# Solar_ESC_AM32.net
KiCad netlist of a schematic drawn in Altium Designer
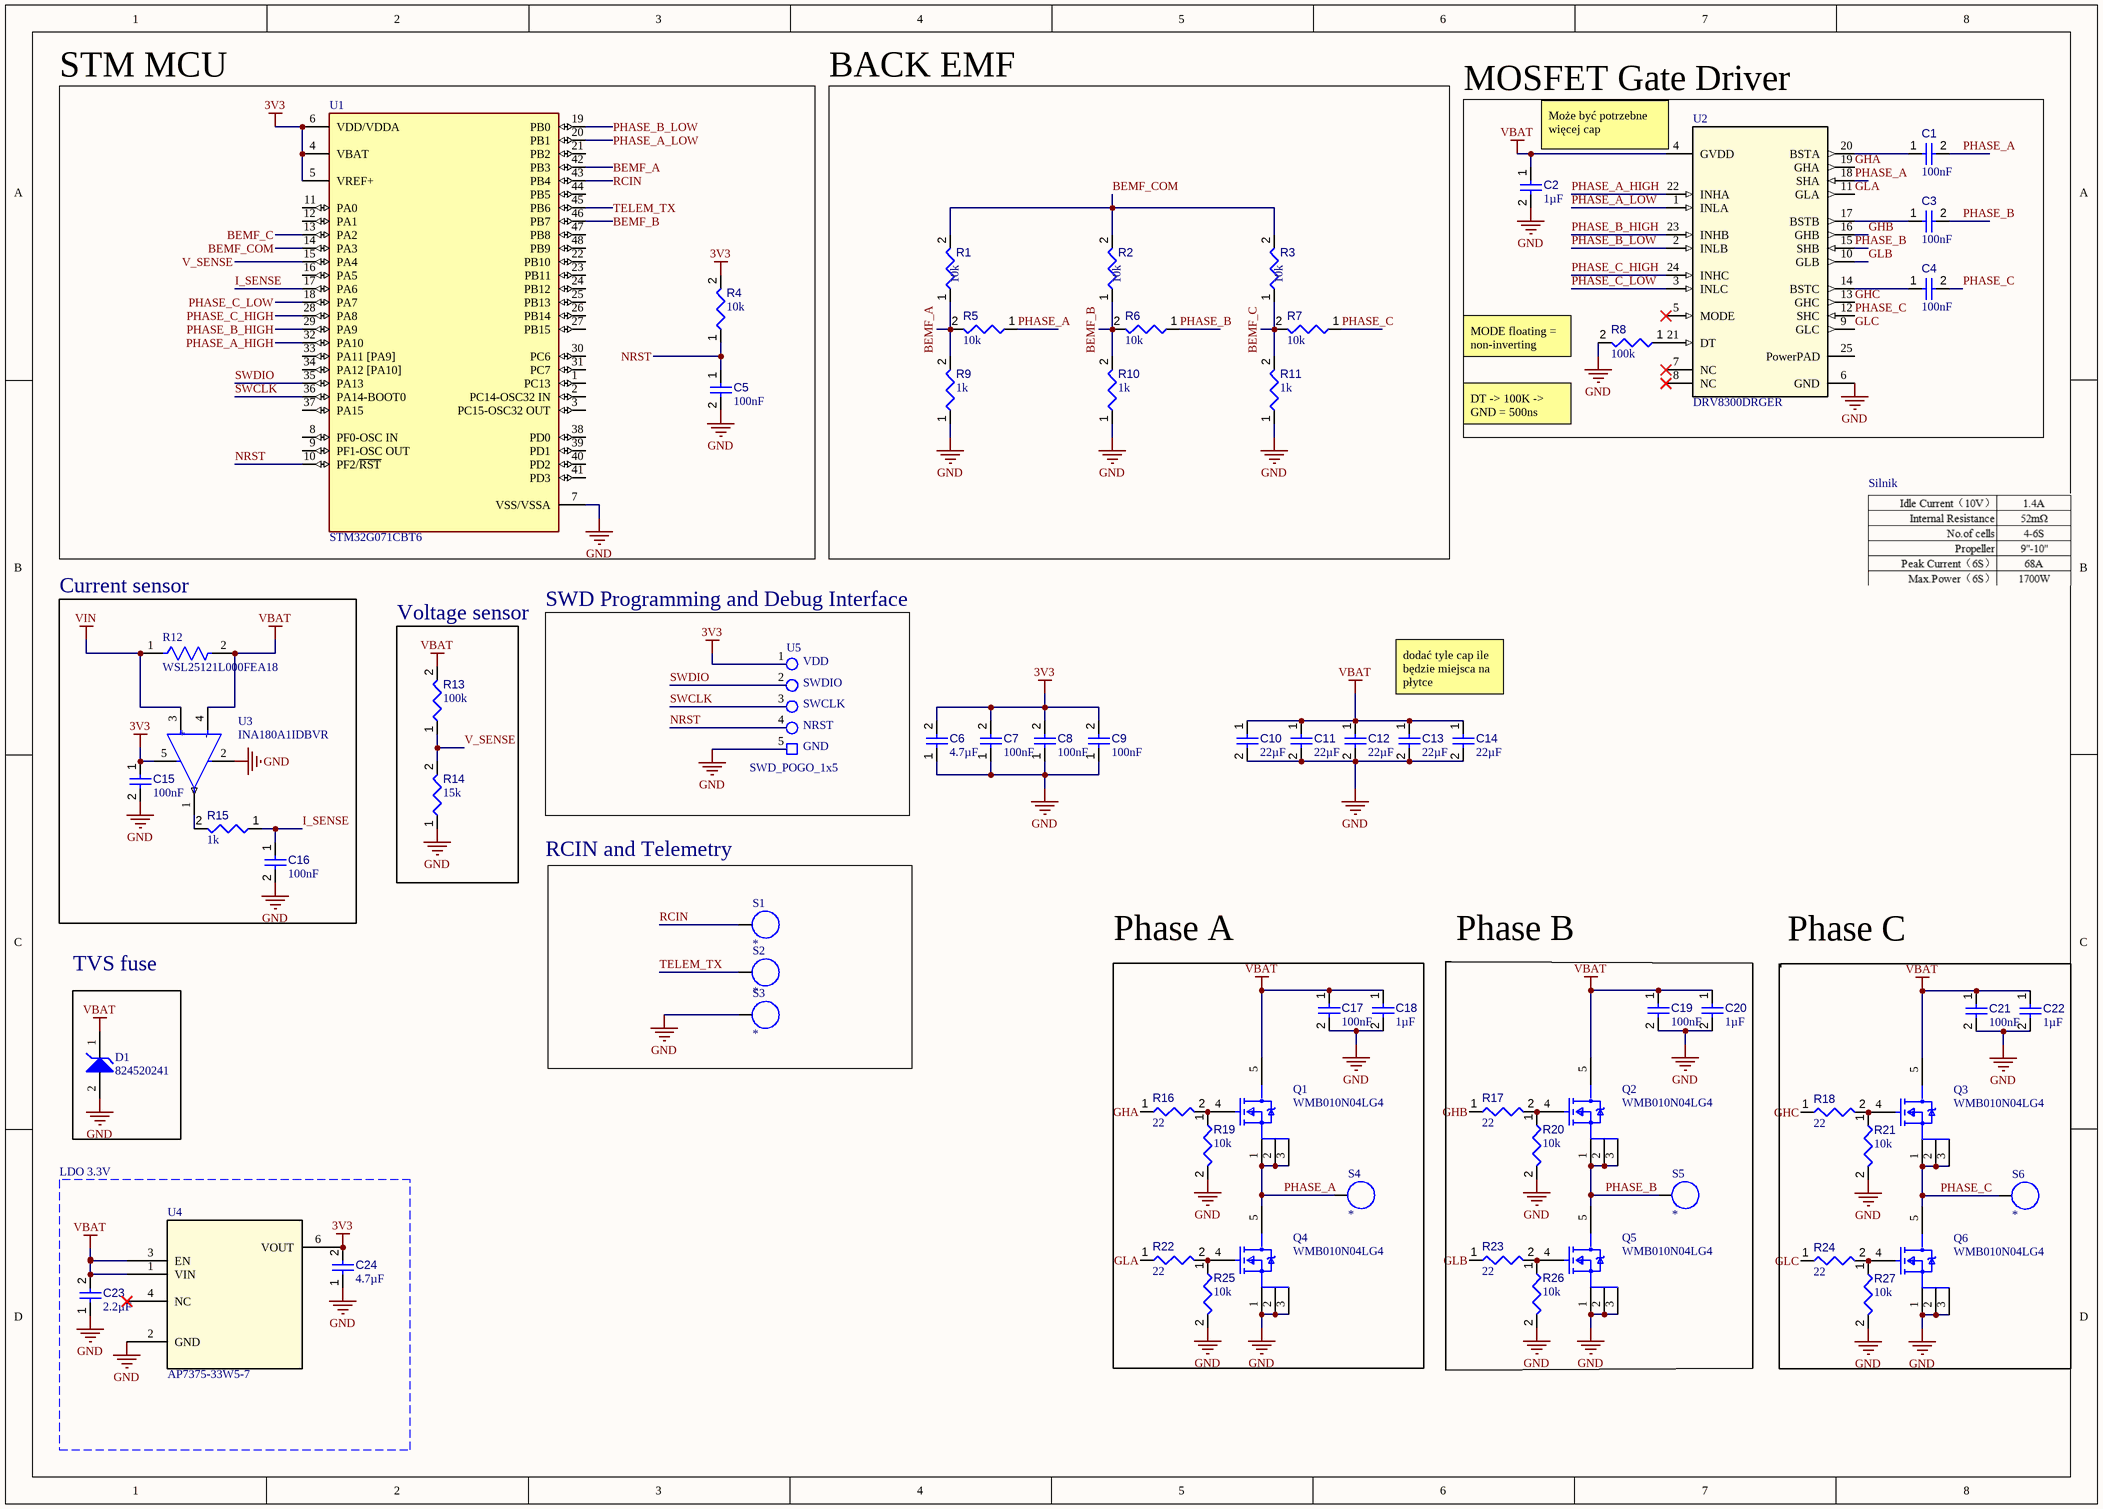
[diagram p0: Solar_ESC_AM32.SchDoc]

(export (version "E")
  (design (tool "Eeschema 10.0.6"))
  (components
    (comp (ref "C1")
      (value "100nF")
      (footprint "CAPC0805(2012)145_L")
      (description "Chip Capacitor, 0.1µF +/-40%, 25V, 0805, Thickness 1.45 mm")
      (fields (field (name "TOLERANCE") "20%") (field (name "Comment") "Capacitor 0.1µF +/-40% 25V 0805"))
      (libsource (lib "Solar_Plane_Jakub_Konior") (part "CAP-NP-2"))
    )
    (comp (ref "C2")
      (value "1µF")
      (footprint "CAPC0805(2012)145_L")
      (description "Chip Capacitor, 1µF +/-40%, 25V, 0805, Thickness 1.45 mm")
      (fields (field (name "TOLERANCE") "20%") (field (name "Comment") "Capacitor 1µF +/-40% 25V 0805"))
      (libsource (lib "Solar_Plane_Jakub_Konior") (part "CAP-NP-2"))
    )
    (comp (ref "C3")
      (value "100nF")
      (footprint "CAPC0805(2012)145_L")
      (description "Chip Capacitor, 0.1µF +/-40%, 25V, 0805, Thickness 1.45 mm")
      (fields (field (name "TOLERANCE") "20%") (field (name "Comment") "Capacitor 0.1µF +/-40% 25V 0805"))
      (libsource (lib "Solar_Plane_Jakub_Konior") (part "CAP-NP-2"))
    )
    (comp (ref "C4")
      (value "100nF")
      (footprint "CAPC0805(2012)145_L")
      (description "Chip Capacitor, 0.1µF +/-40%, 25V, 0805, Thickness 1.45 mm")
      (fields (field (name "TOLERANCE") "20%") (field (name "Comment") "Capacitor 0.1µF +/-40% 25V 0805"))
      (libsource (lib "Solar_Plane_Jakub_Konior") (part "CAP-NP-2"))
    )
    (comp (ref "C5")
      (value "100nF")
      (footprint "CAPC0805(2012)145_L")
      (description "Chip Capacitor, 100nF +/-40%, 6.3V, 0805, Thickness 1.45 mm")
      (fields (field (name "TOLERANCE") "10%") (field (name "Comment") "Capacitor 100nF +/-40% 6.3V 0805"))
      (libsource (lib "Solar_Plane_Jakub_Konior") (part "CAP-NP-2"))
    )
    (comp (ref "C6")
      (value "4.7µF")
      (footprint "CAPC0805(2012)145_L")
      (description "Chip Capacitor, 4.7µF +/-40%, 25V, 0805, Thickness 1.45 mm")
      (fields (field (name "TOLERANCE") "20%") (field (name "Comment") "Capacitor 4.7µF +/-40% 25V 0805"))
      (libsource (lib "Solar_Plane_Jakub_Konior") (part "CAP-NP-2"))
    )
    (comp (ref "C7")
      (value "100nF")
      (footprint "CAPC0805(2012)145_L")
      (description "Chip Capacitor, 0.1µF +/-40%, 25V, 0805, Thickness 1.45 mm")
      (fields (field (name "TOLERANCE") "20%") (field (name "Comment") "Capacitor 0.1µF +/-40% 25V 0805"))
      (libsource (lib "Solar_Plane_Jakub_Konior") (part "CAP-NP-2"))
    )
    (comp (ref "C8")
      (value "100nF")
      (footprint "CAPC0805(2012)145_L")
      (description "Chip Capacitor, 0.1µF +/-40%, 25V, 0805, Thickness 1.45 mm")
      (fields (field (name "TOLERANCE") "20%") (field (name "Comment") "Capacitor 0.1µF +/-40% 25V 0805"))
      (libsource (lib "Solar_Plane_Jakub_Konior") (part "CAP-NP-2"))
    )
    (comp (ref "C9")
      (value "100nF")
      (footprint "CAPC0805(2012)145_L")
      (description "Chip Capacitor, 0.1µF +/-40%, 25V, 0805, Thickness 1.45 mm")
      (fields (field (name "TOLERANCE") "20%") (field (name "Comment") "Capacitor 0.1µF +/-40% 25V 0805"))
      (libsource (lib "Solar_Plane_Jakub_Konior") (part "CAP-NP-2"))
    )
    (comp (ref "C10")
      (value "22µF")
      (footprint "CAPC0805(2012)145_L")
      (description "Chip Capacitor, 22µF +/-40%, 16V, 0805, Thickness 1.45 mm")
      (fields (field (name "TOLERANCE") "5%") (field (name "Comment") "Capacitor 22µF +/-40% 16V 0805"))
      (libsource (lib "Solar_Plane_Jakub_Konior") (part "CAP-NP-2"))
    )
    (comp (ref "C11")
      (value "22µF")
      (footprint "CAPC0805(2012)145_L")
      (description "Chip Capacitor, 22µF +/-40%, 16V, 0805, Thickness 1.45 mm")
      (fields (field (name "TOLERANCE") "5%") (field (name "Comment") "Capacitor 22µF +/-40% 16V 0805"))
      (libsource (lib "Solar_Plane_Jakub_Konior") (part "CAP-NP-2"))
    )
    (comp (ref "C12")
      (value "22µF")
      (footprint "CAPC0805(2012)145_L")
      (description "Chip Capacitor, 22µF +/-40%, 16V, 0805, Thickness 1.45 mm")
      (fields (field (name "TOLERANCE") "5%") (field (name "Comment") "Capacitor 22µF +/-40% 16V 0805"))
      (libsource (lib "Solar_Plane_Jakub_Konior") (part "CAP-NP-2"))
    )
    (comp (ref "C13")
      (value "22µF")
      (footprint "CAPC0805(2012)145_L")
      (description "Chip Capacitor, 22µF +/-40%, 16V, 0805, Thickness 1.45 mm")
      (fields (field (name "TOLERANCE") "5%") (field (name "Comment") "Capacitor 22µF +/-40% 16V 0805"))
      (libsource (lib "Solar_Plane_Jakub_Konior") (part "CAP-NP-2"))
    )
    (comp (ref "C14")
      (value "22µF")
      (footprint "CAPC0805(2012)145_L")
      (description "Chip Capacitor, 22µF +/-40%, 16V, 0805, Thickness 1.45 mm")
      (fields (field (name "TOLERANCE") "5%") (field (name "Comment") "Capacitor 22µF +/-40% 16V 0805"))
      (libsource (lib "Solar_Plane_Jakub_Konior") (part "CAP-NP-2"))
    )
    (comp (ref "C15")
      (value "100nF")
      (footprint "CAPC0805(2012)145_L")
      (description "Chip Capacitor, 0.1µF +/-40%, 25V, 0805, Thickness 1.45 mm")
      (fields (field (name "TOLERANCE") "20%") (field (name "Comment") "Capacitor 0.1µF +/-40% 25V 0805"))
      (libsource (lib "Solar_Plane_Jakub_Konior") (part "CAP-NP-2"))
    )
    (comp (ref "C16")
      (value "100nF")
      (footprint "CAPC0805(2012)145_L")
      (description "Chip Capacitor, 0.1µF +/-40%, 25V, 0805, Thickness 1.45 mm")
      (fields (field (name "TOLERANCE") "20%") (field (name "Comment") "Capacitor 0.1µF +/-40% 25V 0805"))
      (libsource (lib "Solar_Plane_Jakub_Konior") (part "CAP-NP-2"))
    )
    (comp (ref "C17")
      (value "100nF")
      (footprint "CAPC0805(2012)145_L")
      (description "Chip Capacitor, 100nF +/-40%, 6.3V, 0805, Thickness 1.45 mm")
      (fields (field (name "TOLERANCE") "10%") (field (name "Comment") "Capacitor 100nF +/-40% 6.3V 0805"))
      (libsource (lib "Solar_Plane_Jakub_Konior") (part "CAP-NP-2"))
    )
    (comp (ref "C18")
      (value "1µF")
      (footprint "CAPC0805(2012)145_L")
      (description "Chip Capacitor, 1µF +/-40%, 25V, 0805, Thickness 1.45 mm")
      (fields (field (name "TOLERANCE") "20%") (field (name "Comment") "Capacitor 1µF +/-40% 25V 0805"))
      (libsource (lib "Solar_Plane_Jakub_Konior") (part "CAP-NP-2"))
    )
    (comp (ref "C19")
      (value "100nF")
      (footprint "CAPC0805(2012)145_L")
      (description "Chip Capacitor, 100nF +/-40%, 6.3V, 0805, Thickness 1.45 mm")
      (fields (field (name "TOLERANCE") "10%") (field (name "Comment") "Capacitor 100nF +/-40% 6.3V 0805"))
      (libsource (lib "Solar_Plane_Jakub_Konior") (part "CAP-NP-2"))
    )
    (comp (ref "C20")
      (value "1µF")
      (footprint "CAPC0805(2012)145_L")
      (description "Chip Capacitor, 1µF +/-40%, 25V, 0805, Thickness 1.45 mm")
      (fields (field (name "TOLERANCE") "20%") (field (name "Comment") "Capacitor 1µF +/-40% 25V 0805"))
      (libsource (lib "Solar_Plane_Jakub_Konior") (part "CAP-NP-2"))
    )
    (comp (ref "C21")
      (value "100nF")
      (footprint "CAPC0805(2012)145_L")
      (description "Chip Capacitor, 100nF +/-40%, 6.3V, 0805, Thickness 1.45 mm")
      (fields (field (name "TOLERANCE") "10%") (field (name "Comment") "Capacitor 100nF +/-40% 6.3V 0805"))
      (libsource (lib "Solar_Plane_Jakub_Konior") (part "CAP-NP-2"))
    )
    (comp (ref "C22")
      (value "1µF")
      (footprint "CAPC0805(2012)145_L")
      (description "Chip Capacitor, 1µF +/-40%, 25V, 0805, Thickness 1.45 mm")
      (fields (field (name "TOLERANCE") "20%") (field (name "Comment") "Capacitor 1µF +/-40% 25V 0805"))
      (libsource (lib "Solar_Plane_Jakub_Konior") (part "CAP-NP-2"))
    )
    (comp (ref "C23")
      (value "2.2µF")
      (footprint "CAPC0805(2012)145_L")
      (description "Chip Capacitor, 2.2µF +/-40%, 35V, 0805, Thickness 1.45 mm")
      (fields (field (name "TOLERANCE") "20%") (field (name "Comment") "Capacitor 2.2µF +/-40% 35V 0805"))
      (libsource (lib "Solar_Plane_Jakub_Konior") (part "CAP-NP-2"))
    )
    (comp (ref "C24")
      (value "4.7µF")
      (footprint "CAPC0805(2012)145_L")
      (description "Chip Capacitor, 4.7µF +/-40%, 25V, 0805, Thickness 1.45 mm")
      (fields (field (name "TOLERANCE") "20%") (field (name "Comment") "Capacitor 4.7µF +/-40% 25V 0805"))
      (libsource (lib "Solar_Plane_Jakub_Konior") (part "CAP-NP-2"))
    )
    (comp (ref "D1")
      (value "824520241")
      (footprint "WE-TVSP_DO-214AA_Unidirectional")
      (description "TVS diode [Würth Elektronik] 824520241 TVS diode")
      (libsource (lib "Altium Content Vault") (part "WE-TVSP_Unidirectional"))
    )
    (comp (ref "Q1")
      (value "WMB010N04LG4")
      (footprint "TRANS_CMS42N10H8-HF")
      (description "N-MOSFET; unipolar; 40V; 268A; Idm: 1072A; 114W")
      (libsource (lib "Solar_ESC_AM32") (part "WMB010N04LG4"))
    )
    (comp (ref "Q2")
      (value "WMB010N04LG4")
      (footprint "TRANS_CMS42N10H8-HF")
      (description "N-MOSFET; unipolar; 40V; 268A; Idm: 1072A; 114W")
      (libsource (lib "Solar_ESC_AM32") (part "WMB010N04LG4"))
    )
    (comp (ref "Q3")
      (value "WMB010N04LG4")
      (footprint "TRANS_CMS42N10H8-HF")
      (description "N-MOSFET; unipolar; 40V; 268A; Idm: 1072A; 114W")
      (libsource (lib "Solar_ESC_AM32") (part "WMB010N04LG4"))
    )
    (comp (ref "Q4")
      (value "WMB010N04LG4")
      (footprint "TRANS_CMS42N10H8-HF")
      (description "N-MOSFET; unipolar; 40V; 268A; Idm: 1072A; 114W")
      (libsource (lib "Solar_ESC_AM32") (part "WMB010N04LG4"))
    )
    (comp (ref "Q5")
      (value "WMB010N04LG4")
      (footprint "TRANS_CMS42N10H8-HF")
      (description "N-MOSFET; unipolar; 40V; 268A; Idm: 1072A; 114W")
      (libsource (lib "Solar_ESC_AM32") (part "WMB010N04LG4"))
    )
    (comp (ref "Q6")
      (value "WMB010N04LG4")
      (footprint "TRANS_CMS42N10H8-HF")
      (description "N-MOSFET; unipolar; 40V; 268A; Idm: 1072A; 114W")
      (libsource (lib "Solar_ESC_AM32") (part "WMB010N04LG4"))
    )
    (comp (ref "R1")
      (value "10k")
      (footprint "RESC0402(1005)_L")
      (description "Chip Resistor, 10 kOhms, +/-1 %, 63 mW, -55 to 125 degC, 0402")
      (fields (field (name "POWER") "63mW") (field (name "TOLERANCE") "1%"))
      (libsource (lib "Solar_Plane_Jakub_Konior") (part "RES-2"))
    )
    (comp (ref "R2")
      (value "10k")
      (footprint "RESC0402(1005)_L")
      (description "Chip Resistor, 10 kOhms, +/-1 %, 63 mW, -55 to 125 degC, 0402")
      (fields (field (name "POWER") "63mW") (field (name "TOLERANCE") "1%"))
      (libsource (lib "Solar_Plane_Jakub_Konior") (part "RES-2"))
    )
    (comp (ref "R3")
      (value "10k")
      (footprint "RESC0402(1005)_L")
      (description "Chip Resistor, 10 kOhms, +/-1 %, 63 mW, -55 to 125 degC, 0402")
      (fields (field (name "POWER") "63mW") (field (name "TOLERANCE") "1%"))
      (libsource (lib "Solar_Plane_Jakub_Konior") (part "RES-2"))
    )
    (comp (ref "R4")
      (value "10k")
      (footprint "RESC0402(1005)_L")
      (description "Chip Resistor, 10 kOhms, +/-1 %, 63 mW, -55 to 125 degC, 0402")
      (fields (field (name "POWER") "63mW") (field (name "TOLERANCE") "1%"))
      (libsource (lib "Solar_Plane_Jakub_Konior") (part "RES-2"))
    )
    (comp (ref "R5")
      (value "10k")
      (footprint "RESC0402(1005)_L")
      (description "Chip Resistor, 10 kOhms, +/-1 %, 63 mW, -55 to 125 degC, 0402")
      (fields (field (name "POWER") "63mW") (field (name "TOLERANCE") "1%"))
      (libsource (lib "Solar_Plane_Jakub_Konior") (part "RES-2"))
    )
    (comp (ref "R6")
      (value "10k")
      (footprint "RESC0402(1005)_L")
      (description "Chip Resistor, 10 kOhms, +/-1 %, 63 mW, -55 to 125 degC, 0402")
      (fields (field (name "POWER") "63mW") (field (name "TOLERANCE") "1%"))
      (libsource (lib "Solar_Plane_Jakub_Konior") (part "RES-2"))
    )
    (comp (ref "R7")
      (value "10k")
      (footprint "RESC0402(1005)_L")
      (description "Chip Resistor, 10 kOhms, +/-1 %, 63 mW, -55 to 125 degC, 0402")
      (fields (field (name "POWER") "63mW") (field (name "TOLERANCE") "1%"))
      (libsource (lib "Solar_Plane_Jakub_Konior") (part "RES-2"))
    )
    (comp (ref "R8")
      (value "100k")
      (footprint "RESC0402(1005)_L")
      (description "Chip Resistor, 100 kOhms, +/-1 %, 63 mW, -55 to 155 degC, 0402")
      (fields (field (name "TOLERANCE") "1%") (field (name "POWER") "63mW"))
      (libsource (lib "Solar_Plane_Jakub_Konior") (part "RES-2"))
    )
    (comp (ref "R9")
      (value "1k")
      (footprint "RESC0402(1005)_L")
      (description "Chip Resistor, 1 kOhms, +/-5 %, 63 mW, -55 to 155 degC, 0402")
      (fields (field (name "TOLERANCE") "5%") (field (name "POWER") "63mW"))
      (libsource (lib "Solar_Plane_Jakub_Konior") (part "RES-2"))
    )
    (comp (ref "R10")
      (value "1k")
      (footprint "RESC0402(1005)_L")
      (description "Chip Resistor, 1 kOhms, +/-5 %, 63 mW, -55 to 155 degC, 0402")
      (fields (field (name "TOLERANCE") "5%") (field (name "POWER") "63mW"))
      (libsource (lib "Solar_Plane_Jakub_Konior") (part "RES-2"))
    )
    (comp (ref "R11")
      (value "1k")
      (footprint "RESC0402(1005)_L")
      (description "Chip Resistor, 1 kOhms, +/-5 %, 63 mW, -55 to 155 degC, 0402")
      (fields (field (name "TOLERANCE") "5%") (field (name "POWER") "63mW"))
      (libsource (lib "Solar_Plane_Jakub_Konior") (part "RES-2"))
    )
    (comp (ref "R12")
      (value "WSL25121L000FEA18")
      (footprint "FP-WSL2512-MFG")
      (fields (field (name "TOLERANCE") "1%"))
      (libsource (lib "Altium Content Vault") (part "1029c3af85768c4190bb7ad29bc67b5"))
    )
    (comp (ref "R13")
      (value "100k")
      (footprint "RESC0402(1005)_L")
      (description "Chip Resistor, 100 kOhms, +/-1 %, 63 mW, -55 to 155 degC, 0402")
      (fields (field (name "TOLERANCE") "1%") (field (name "POWER") "63mW"))
      (libsource (lib "Solar_Plane_Jakub_Konior") (part "RES-2"))
    )
    (comp (ref "R14")
      (value "15k")
      (footprint "RESC0402(1005)_L")
      (description "Chip Resistor, 15 kOhms, +/-1 %, 63 mW, -55 to 155 degC, 0402")
      (fields (field (name "TOLERANCE") "1%") (field (name "POWER") "63mW"))
      (libsource (lib "Solar_Plane_Jakub_Konior") (part "RES-2"))
    )
    (comp (ref "R15")
      (value "1k")
      (footprint "RESC0402(1005)_L")
      (description "Chip Resistor, 1 kOhms, +/-5 %, 63 mW, -55 to 155 degC, 0402")
      (fields (field (name "TOLERANCE") "5%") (field (name "POWER") "63mW"))
      (libsource (lib "Solar_Plane_Jakub_Konior") (part "RES-2"))
    )
    (comp (ref "R16")
      (value "22")
      (footprint "RESC1609X50X30ML08T20")
      (description "Chip Resistor, 22 Ohm, +/- 1%, 100 mW, -55 to 155 degC, 0603 (1608 Metric)")
      (fields (field (name "POWER") "100mW") (field (name "TOLERANCE") "1%"))
      (libsource (lib "Solar_Plane_Jakub_Konior") (part "RES-2"))
    )
    (comp (ref "R17")
      (value "22")
      (footprint "RESC1609X50X30ML08T20")
      (description "Chip Resistor, 22 Ohm, +/- 1%, 100 mW, -55 to 155 degC, 0603 (1608 Metric)")
      (fields (field (name "POWER") "100mW") (field (name "TOLERANCE") "1%"))
      (libsource (lib "Solar_Plane_Jakub_Konior") (part "RES-2"))
    )
    (comp (ref "R18")
      (value "22")
      (footprint "RESC1609X50X30ML08T20")
      (description "Chip Resistor, 22 Ohm, +/- 1%, 100 mW, -55 to 155 degC, 0603 (1608 Metric)")
      (fields (field (name "POWER") "100mW") (field (name "TOLERANCE") "1%"))
      (libsource (lib "Solar_Plane_Jakub_Konior") (part "RES-2"))
    )
    (comp (ref "R19")
      (value "10k")
      (footprint "RESC0402(1005)_L")
      (description "Chip Resistor, 10 kOhms, +/-1 %, 63 mW, -55 to 125 degC, 0402")
      (fields (field (name "POWER") "63mW") (field (name "TOLERANCE") "1%"))
      (libsource (lib "Solar_Plane_Jakub_Konior") (part "RES-2"))
    )
    (comp (ref "R20")
      (value "10k")
      (footprint "RESC0402(1005)_L")
      (description "Chip Resistor, 10 kOhms, +/-1 %, 63 mW, -55 to 125 degC, 0402")
      (fields (field (name "POWER") "63mW") (field (name "TOLERANCE") "1%"))
      (libsource (lib "Solar_Plane_Jakub_Konior") (part "RES-2"))
    )
    (comp (ref "R21")
      (value "10k")
      (footprint "RESC0402(1005)_L")
      (description "Chip Resistor, 10 kOhms, +/-1 %, 63 mW, -55 to 125 degC, 0402")
      (fields (field (name "POWER") "63mW") (field (name "TOLERANCE") "1%"))
      (libsource (lib "Solar_Plane_Jakub_Konior") (part "RES-2"))
    )
    (comp (ref "R22")
      (value "22")
      (footprint "RESC1609X50X30ML08T20")
      (description "Chip Resistor, 22 Ohm, +/- 1%, 100 mW, -55 to 155 degC, 0603 (1608 Metric)")
      (fields (field (name "POWER") "100mW") (field (name "TOLERANCE") "1%"))
      (libsource (lib "Solar_Plane_Jakub_Konior") (part "RES-2"))
    )
    (comp (ref "R23")
      (value "22")
      (footprint "RESC1609X50X30ML08T20")
      (description "Chip Resistor, 22 Ohm, +/- 1%, 100 mW, -55 to 155 degC, 0603 (1608 Metric)")
      (fields (field (name "POWER") "100mW") (field (name "TOLERANCE") "1%"))
      (libsource (lib "Solar_Plane_Jakub_Konior") (part "RES-2"))
    )
    (comp (ref "R24")
      (value "22")
      (footprint "RESC1609X50X30ML08T20")
      (description "Chip Resistor, 22 Ohm, +/- 1%, 100 mW, -55 to 155 degC, 0603 (1608 Metric)")
      (fields (field (name "POWER") "100mW") (field (name "TOLERANCE") "1%"))
      (libsource (lib "Solar_Plane_Jakub_Konior") (part "RES-2"))
    )
    (comp (ref "R25")
      (value "10k")
      (footprint "RESC0402(1005)_L")
      (description "Chip Resistor, 10 kOhms, +/-1 %, 63 mW, -55 to 125 degC, 0402")
      (fields (field (name "POWER") "63mW") (field (name "TOLERANCE") "1%"))
      (libsource (lib "Solar_Plane_Jakub_Konior") (part "RES-2"))
    )
    (comp (ref "R26")
      (value "10k")
      (footprint "RESC0402(1005)_L")
      (description "Chip Resistor, 10 kOhms, +/-1 %, 63 mW, -55 to 125 degC, 0402")
      (fields (field (name "POWER") "63mW") (field (name "TOLERANCE") "1%"))
      (libsource (lib "Solar_Plane_Jakub_Konior") (part "RES-2"))
    )
    (comp (ref "R27")
      (value "10k")
      (footprint "RESC0402(1005)_L")
      (description "Chip Resistor, 10 kOhms, +/-1 %, 63 mW, -55 to 125 degC, 0402")
      (fields (field (name "POWER") "63mW") (field (name "TOLERANCE") "1%"))
      (libsource (lib "Solar_Plane_Jakub_Konior") (part "RES-2"))
    )
    (comp (ref "S1")
      (value "*")
      (footprint "SOLDER_PAD_SIGNAL")
      (libsource (lib "Solar_ESC_AM32") (part "SolderPad"))
    )
    (comp (ref "S2")
      (value "*")
      (footprint "SOLDER_PAD_SIGNAL")
      (libsource (lib "Solar_ESC_AM32") (part "SolderPad"))
    )
    (comp (ref "S3")
      (value "*")
      (footprint "SOLDER_PAD_SIGNAL")
      (libsource (lib "Solar_ESC_AM32") (part "SolderPad"))
    )
    (comp (ref "S4")
      (value "*")
      (footprint "SOLDER_PAD_PHASE")
      (libsource (lib "Solar_ESC_AM32") (part "SolderPad"))
    )
    (comp (ref "S5")
      (value "*")
      (footprint "SOLDER_PAD_PHASE")
      (libsource (lib "Solar_ESC_AM32") (part "SolderPad"))
    )
    (comp (ref "S6")
      (value "*")
      (footprint "SOLDER_PAD_PHASE")
      (libsource (lib "Solar_ESC_AM32") (part "SolderPad"))
    )
    (comp (ref "U1")
      (value "STM32G071CBT6")
      (footprint "FP-LQFP48-5B-MFG")
      (description "IC MCU 32BIT 128KB FLASH 48LQFP")
      (fields
        (field (name "OCTOPART") "https://octopart.com/stm32g071cbt6-stmicroelectronics-96627027")
        (field (name "MANUFACTURER") "STMicroelectronics")
      )
      (libsource (lib "Altium Content Vault") (part "c9f63a35dbd129b66bfedb266152198"))
    )
    (comp (ref "U2")
      (value "DRV8300DRGER")
      (footprint "RGE0024B-IPC_B")
      (description "100-V max simple 3-phase gate driver with bootstrap diodes 24-VQFN -40 to 125")
      (fields (field (name "COPYRIGHT") "Copyright (C) 2025 Ultra Librarian. All rights reserved."))
      (libsource (lib "Solar_ESC_AM32") (part "DRV8300DRGER"))
    )
    (comp (ref "U3")
      (value "INA180A1IDBVR")
      (footprint "FP-DBV0005A-IPC_A")
      (description "IC CURR SENSE 1 CIRCUIT SOT23-5")
      (libsource (lib "Altium Content Vault") (part "0a55cf1a948ad01a3239aec1b7efad0"))
    )
    (comp (ref "U4")
      (value "AP7375-33W5-7")
      (footprint "SOT25_AP7375-33W5-7_DIO")
      (description "Description")
      (fields (field (name "COPYRIGHT") "Copyright (C) 2026 Ultra Librarian. All rights reserved."))
      (libsource (lib "AP7375-33W5-7") (part "AP7375-33W5-7"))
    )
    (comp (ref "U5")
      (value "SWD_POGO_1x5")
      (footprint "SWD_pogo_testpoints")
      (libsource (lib "Solar_ESC_AM32") (part "SWD_POGO_1x5"))
    )
  )
  (nets
    (net (code "2") (name "/BEMF_A") (class "Default")
      (node (ref "R1") (pin "1") (pinfunction "1_1") (pintype "passive"))
      (node (ref "R5") (pin "2") (pinfunction "2_2") (pintype "passive"))
      (node (ref "R9") (pin "2") (pinfunction "2_2") (pintype "passive"))
      (node (ref "U1") (pin "42") (pinfunction "PB3_42") (pintype "bidirectional"))
    )
    (net (code "3") (name "/BEMF_B") (class "Default")
      (node (ref "R10") (pin "2") (pinfunction "2_2") (pintype "passive"))
      (node (ref "R2") (pin "1") (pinfunction "1_1") (pintype "passive"))
      (node (ref "R6") (pin "2") (pinfunction "2_2") (pintype "passive"))
      (node (ref "U1") (pin "46") (pinfunction "PB7_46") (pintype "bidirectional"))
    )
    (net (code "4") (name "/BEMF_C") (class "Default")
      (node (ref "R11") (pin "2") (pinfunction "2_2") (pintype "passive"))
      (node (ref "R3") (pin "1") (pinfunction "1_1") (pintype "passive"))
      (node (ref "R7") (pin "2") (pinfunction "2_2") (pintype "passive"))
      (node (ref "U1") (pin "13") (pinfunction "PA2_13") (pintype "bidirectional"))
    )
    (net (code "5") (name "/BEMF_COM") (class "Default")
      (node (ref "R1") (pin "2") (pinfunction "2_2") (pintype "passive"))
      (node (ref "R2") (pin "2") (pinfunction "2_2") (pintype "passive"))
      (node (ref "R3") (pin "2") (pinfunction "2_2") (pintype "passive"))
      (node (ref "U1") (pin "14") (pinfunction "PA3_14") (pintype "bidirectional"))
    )
    (net (code "6") (name "/GHA") (class "Default")
      (node (ref "R16") (pin "1") (pinfunction "1_1") (pintype "passive"))
      (node (ref "U2") (pin "19") (pinfunction "GHA_19") (pintype "output"))
    )
    (net (code "7") (name "/GHB") (class "Default")
      (node (ref "R17") (pin "1") (pinfunction "1_1") (pintype "passive"))
      (node (ref "U2") (pin "16") (pinfunction "GHB_16") (pintype "output"))
    )
    (net (code "8") (name "/GHC") (class "Default")
      (node (ref "R18") (pin "1") (pinfunction "1_1") (pintype "passive"))
      (node (ref "U2") (pin "13") (pinfunction "GHC_13") (pintype "output"))
    )
    (net (code "9") (name "/GLA") (class "Default")
      (node (ref "R22") (pin "1") (pinfunction "1_1") (pintype "passive"))
      (node (ref "U2") (pin "11") (pinfunction "GLA_11") (pintype "output"))
    )
    (net (code "10") (name "/GLB") (class "Default")
      (node (ref "R23") (pin "1") (pinfunction "1_1") (pintype "passive"))
      (node (ref "U2") (pin "10") (pinfunction "GLB_10") (pintype "output"))
    )
    (net (code "11") (name "/GLC") (class "Default")
      (node (ref "R24") (pin "1") (pinfunction "1_1") (pintype "passive"))
      (node (ref "U2") (pin "9") (pinfunction "GLC_9") (pintype "output"))
    )
    (net (code "12") (name "/I_SENSE") (class "Default")
      (node (ref "C16") (pin "1") (pinfunction "1_1") (pintype "passive"))
      (node (ref "R15") (pin "1") (pinfunction "1_1") (pintype "passive"))
      (node (ref "U1") (pin "17") (pinfunction "PA6_17") (pintype "bidirectional"))
    )
    (net (code "13") (name "/NRST") (class "Default")
      (node (ref "C5") (pin "1") (pinfunction "1_1") (pintype "passive"))
      (node (ref "R4") (pin "1") (pinfunction "1_1") (pintype "passive"))
      (node (ref "U1") (pin "10") (pinfunction "PF2/~{RST}_10") (pintype "bidirectional"))
      (node (ref "U5") (pin "4") (pinfunction "NRST_4") (pintype "passive"))
    )
    (net (code "14") (name "/PHASE_A") (class "Default")
      (node (ref "C1") (pin "2") (pinfunction "2_2") (pintype "passive"))
      (node (ref "Q1") (pin "1") (pinfunction "S_1") (pintype "passive"))
      (node (ref "Q1") (pin "2") (pinfunction "S_2") (pintype "passive"))
      (node (ref "Q1") (pin "3") (pinfunction "S_3") (pintype "passive"))
      (node (ref "Q4") (pin "5") (pinfunction "D_5") (pintype "passive"))
      (node (ref "R5") (pin "1") (pinfunction "1_1") (pintype "passive"))
      (node (ref "S4") (pin "1") (pintype "passive"))
      (node (ref "U2") (pin "18") (pinfunction "SHA_18") (pintype "input"))
    )
    (net (code "15") (name "/PHASE_A_HIGH") (class "Default")
      (node (ref "U1") (pin "32") (pinfunction "PA10_32") (pintype "bidirectional"))
      (node (ref "U2") (pin "22") (pinfunction "INHA_22") (pintype "input"))
    )
    (net (code "16") (name "/PHASE_A_LOW") (class "Default")
      (node (ref "U1") (pin "20") (pinfunction "PB1_20") (pintype "bidirectional"))
      (node (ref "U2") (pin "1") (pinfunction "INLA_1") (pintype "input"))
    )
    (net (code "17") (name "/PHASE_B") (class "Default")
      (node (ref "C3") (pin "2") (pinfunction "2_2") (pintype "passive"))
      (node (ref "Q2") (pin "1") (pinfunction "S_1") (pintype "passive"))
      (node (ref "Q2") (pin "2") (pinfunction "S_2") (pintype "passive"))
      (node (ref "Q2") (pin "3") (pinfunction "S_3") (pintype "passive"))
      (node (ref "Q5") (pin "5") (pinfunction "D_5") (pintype "passive"))
      (node (ref "R6") (pin "1") (pinfunction "1_1") (pintype "passive"))
      (node (ref "S5") (pin "1") (pintype "passive"))
      (node (ref "U2") (pin "15") (pinfunction "SHB_15") (pintype "input"))
    )
    (net (code "18") (name "/PHASE_B_HIGH") (class "Default")
      (node (ref "U1") (pin "29") (pinfunction "PA9_29") (pintype "bidirectional"))
      (node (ref "U2") (pin "23") (pinfunction "INHB_23") (pintype "input"))
    )
    (net (code "19") (name "/PHASE_B_LOW") (class "Default")
      (node (ref "U1") (pin "19") (pinfunction "PB0_19") (pintype "bidirectional"))
      (node (ref "U2") (pin "2") (pinfunction "INLB_2") (pintype "input"))
    )
    (net (code "20") (name "/PHASE_C") (class "Default")
      (node (ref "C4") (pin "2") (pinfunction "2_2") (pintype "passive"))
      (node (ref "Q3") (pin "1") (pinfunction "S_1") (pintype "passive"))
      (node (ref "Q3") (pin "2") (pinfunction "S_2") (pintype "passive"))
      (node (ref "Q3") (pin "3") (pinfunction "S_3") (pintype "passive"))
      (node (ref "Q6") (pin "5") (pinfunction "D_5") (pintype "passive"))
      (node (ref "R7") (pin "1") (pinfunction "1_1") (pintype "passive"))
      (node (ref "S6") (pin "1") (pintype "passive"))
      (node (ref "U2") (pin "12") (pinfunction "SHC_12") (pintype "input"))
    )
    (net (code "21") (name "/PHASE_C_HIGH") (class "Default")
      (node (ref "U1") (pin "28") (pinfunction "PA8_28") (pintype "bidirectional"))
      (node (ref "U2") (pin "24") (pinfunction "INHC_24") (pintype "input"))
    )
    (net (code "22") (name "/PHASE_C_LOW") (class "Default")
      (node (ref "U1") (pin "18") (pinfunction "PA7_18") (pintype "bidirectional"))
      (node (ref "U2") (pin "3") (pinfunction "INLC_3") (pintype "input"))
    )
    (net (code "23") (name "/RCIN") (class "Default")
      (node (ref "S1") (pin "1") (pintype "passive"))
      (node (ref "U1") (pin "43") (pinfunction "PB4_43") (pintype "bidirectional"))
    )
    (net (code "24") (name "/SWCLK") (class "Default")
      (node (ref "U1") (pin "36") (pinfunction "PA14-BOOT0_36") (pintype "bidirectional"))
      (node (ref "U5") (pin "3") (pinfunction "SWCLK_3") (pintype "passive"))
    )
    (net (code "25") (name "/SWDIO") (class "Default")
      (node (ref "U1") (pin "35") (pinfunction "PA13_35") (pintype "bidirectional"))
      (node (ref "U5") (pin "2") (pinfunction "SWDIO_2") (pintype "passive"))
    )
    (net (code "26") (name "/TELEM_TX") (class "Default")
      (node (ref "S2") (pin "1") (pintype "passive"))
      (node (ref "U1") (pin "45") (pinfunction "PB6_45") (pintype "bidirectional"))
    )
    (net (code "27") (name "/V_SENSE") (class "Default")
      (node (ref "R13") (pin "1") (pinfunction "1_1") (pintype "passive"))
      (node (ref "R14") (pin "2") (pinfunction "2_2") (pintype "passive"))
      (node (ref "U1") (pin "15") (pinfunction "PA4_15") (pintype "bidirectional"))
    )
    (net (code "28") (name "3V3") (class "Default")
      (node (ref "C15") (pin "1") (pinfunction "1_1") (pintype "passive"))
      (node (ref "C24") (pin "2") (pinfunction "2_2") (pintype "passive"))
      (node (ref "C6") (pin "2") (pinfunction "2_2") (pintype "passive"))
      (node (ref "C7") (pin "2") (pinfunction "2_2") (pintype "passive"))
      (node (ref "C8") (pin "2") (pinfunction "2_2") (pintype "passive"))
      (node (ref "C9") (pin "2") (pinfunction "2_2") (pintype "passive"))
      (node (ref "R4") (pin "2") (pinfunction "2_2") (pintype "passive"))
      (node (ref "U1") (pin "4") (pinfunction "VBAT_4") (pintype "power_in"))
      (node (ref "U1") (pin "5") (pinfunction "VREF+_5") (pintype "power_in"))
      (node (ref "U1") (pin "6") (pinfunction "VDD/VDDA_6") (pintype "power_in"))
      (node (ref "U3") (pin "5") (pinfunction "VS_5") (pintype "power_in"))
      (node (ref "U4") (pin "6") (pinfunction "VOUT_6") (pintype "power_in"))
      (node (ref "U5") (pin "1") (pinfunction "VCC_1") (pintype "passive"))
    )
    (net (code "29") (name "GND") (class "Default")
      (node (ref "C10") (pin "2") (pinfunction "2_2") (pintype "passive"))
      (node (ref "C11") (pin "2") (pinfunction "2_2") (pintype "passive"))
      (node (ref "C12") (pin "2") (pinfunction "2_2") (pintype "passive"))
      (node (ref "C13") (pin "2") (pinfunction "2_2") (pintype "passive"))
      (node (ref "C14") (pin "2") (pinfunction "2_2") (pintype "passive"))
      (node (ref "C15") (pin "2") (pinfunction "2_2") (pintype "passive"))
      (node (ref "C16") (pin "2") (pinfunction "2_2") (pintype "passive"))
      (node (ref "C17") (pin "2") (pinfunction "2_2") (pintype "passive"))
      (node (ref "C18") (pin "2") (pinfunction "2_2") (pintype "passive"))
      (node (ref "C19") (pin "2") (pinfunction "2_2") (pintype "passive"))
      (node (ref "C2") (pin "2") (pinfunction "2_2") (pintype "passive"))
      (node (ref "C20") (pin "2") (pinfunction "2_2") (pintype "passive"))
      (node (ref "C21") (pin "2") (pinfunction "2_2") (pintype "passive"))
      (node (ref "C22") (pin "2") (pinfunction "2_2") (pintype "passive"))
      (node (ref "C23") (pin "1") (pinfunction "1_1") (pintype "passive"))
      (node (ref "C24") (pin "1") (pinfunction "1_1") (pintype "passive"))
      (node (ref "C5") (pin "2") (pinfunction "2_2") (pintype "passive"))
      (node (ref "C6") (pin "1") (pinfunction "1_1") (pintype "passive"))
      (node (ref "C7") (pin "1") (pinfunction "1_1") (pintype "passive"))
      (node (ref "C8") (pin "1") (pinfunction "1_1") (pintype "passive"))
      (node (ref "C9") (pin "1") (pinfunction "1_1") (pintype "passive"))
      (node (ref "D1") (pin "2") (pinfunction "A_2") (pintype "passive"))
      (node (ref "Q4") (pin "1") (pinfunction "S_1") (pintype "passive"))
      (node (ref "Q4") (pin "2") (pinfunction "S_2") (pintype "passive"))
      (node (ref "Q4") (pin "3") (pinfunction "S_3") (pintype "passive"))
      (node (ref "Q5") (pin "1") (pinfunction "S_1") (pintype "passive"))
      (node (ref "Q5") (pin "2") (pinfunction "S_2") (pintype "passive"))
      (node (ref "Q5") (pin "3") (pinfunction "S_3") (pintype "passive"))
      (node (ref "Q6") (pin "1") (pinfunction "S_1") (pintype "passive"))
      (node (ref "Q6") (pin "2") (pinfunction "S_2") (pintype "passive"))
      (node (ref "Q6") (pin "3") (pinfunction "S_3") (pintype "passive"))
      (node (ref "R10") (pin "1") (pinfunction "1_1") (pintype "passive"))
      (node (ref "R11") (pin "1") (pinfunction "1_1") (pintype "passive"))
      (node (ref "R14") (pin "1") (pinfunction "1_1") (pintype "passive"))
      (node (ref "R19") (pin "2") (pinfunction "2_2") (pintype "passive"))
      (node (ref "R20") (pin "2") (pinfunction "2_2") (pintype "passive"))
      (node (ref "R21") (pin "2") (pinfunction "2_2") (pintype "passive"))
      (node (ref "R25") (pin "2") (pinfunction "2_2") (pintype "passive"))
      (node (ref "R26") (pin "2") (pinfunction "2_2") (pintype "passive"))
      (node (ref "R27") (pin "2") (pinfunction "2_2") (pintype "passive"))
      (node (ref "R8") (pin "2") (pinfunction "2_2") (pintype "passive"))
      (node (ref "R9") (pin "1") (pinfunction "1_1") (pintype "passive"))
      (node (ref "S3") (pin "1") (pintype "passive"))
      (node (ref "U1") (pin "7") (pinfunction "VSS/VSSA_7") (pintype "power_in"))
      (node (ref "U2") (pin "6") (pinfunction "GND_6") (pintype "power_in"))
      (node (ref "U3") (pin "2") (pinfunction "GND_2") (pintype "power_in"))
      (node (ref "U4") (pin "2") (pinfunction "GND_2") (pintype "power_in"))
      (node (ref "U5") (pin "5") (pinfunction "GND_5") (pintype "passive"))
    )
    (net (code "30") (name "Net-(Q1-G)") (class "Default")
      (node (ref "Q1") (pin "4") (pinfunction "G_4") (pintype "passive"))
      (node (ref "R16") (pin "2") (pinfunction "2_2") (pintype "passive"))
      (node (ref "R19") (pin "1") (pinfunction "1_1") (pintype "passive"))
    )
    (net (code "31") (name "Net-(Q2-G)") (class "Default")
      (node (ref "Q2") (pin "4") (pinfunction "G_4") (pintype "passive"))
      (node (ref "R17") (pin "2") (pinfunction "2_2") (pintype "passive"))
      (node (ref "R20") (pin "1") (pinfunction "1_1") (pintype "passive"))
    )
    (net (code "32") (name "Net-(Q3-G)") (class "Default")
      (node (ref "Q3") (pin "4") (pinfunction "G_4") (pintype "passive"))
      (node (ref "R18") (pin "2") (pinfunction "2_2") (pintype "passive"))
      (node (ref "R21") (pin "1") (pinfunction "1_1") (pintype "passive"))
    )
    (net (code "33") (name "Net-(Q4-G)") (class "Default")
      (node (ref "Q4") (pin "4") (pinfunction "G_4") (pintype "passive"))
      (node (ref "R22") (pin "2") (pinfunction "2_2") (pintype "passive"))
      (node (ref "R25") (pin "1") (pinfunction "1_1") (pintype "passive"))
    )
    (net (code "34") (name "Net-(Q5-G)") (class "Default")
      (node (ref "Q5") (pin "4") (pinfunction "G_4") (pintype "passive"))
      (node (ref "R23") (pin "2") (pinfunction "2_2") (pintype "passive"))
      (node (ref "R26") (pin "1") (pinfunction "1_1") (pintype "passive"))
    )
    (net (code "35") (name "Net-(Q6-G)") (class "Default")
      (node (ref "Q6") (pin "4") (pinfunction "G_4") (pintype "passive"))
      (node (ref "R24") (pin "2") (pinfunction "2_2") (pintype "passive"))
      (node (ref "R27") (pin "1") (pinfunction "1_1") (pintype "passive"))
    )
    (net (code "36") (name "Net-(U2-BSTA)") (class "Default")
      (node (ref "C1") (pin "1") (pinfunction "1_1") (pintype "passive"))
      (node (ref "U2") (pin "20") (pinfunction "BSTA_20") (pintype "output"))
    )
    (net (code "37") (name "Net-(U2-BSTB)") (class "Default")
      (node (ref "C3") (pin "1") (pinfunction "1_1") (pintype "passive"))
      (node (ref "U2") (pin "17") (pinfunction "BSTB_17") (pintype "output"))
    )
    (net (code "38") (name "Net-(U2-BSTC)") (class "Default")
      (node (ref "C4") (pin "1") (pinfunction "1_1") (pintype "passive"))
      (node (ref "U2") (pin "14") (pinfunction "BSTC_14") (pintype "output"))
    )
    (net (code "39") (name "Net-(U2-DT)") (class "Default")
      (node (ref "R8") (pin "1") (pinfunction "1_1") (pintype "passive"))
      (node (ref "U2") (pin "21") (pinfunction "DT_21") (pintype "input"))
    )
    (net (code "40") (name "Net-(U3-OUT)") (class "Default")
      (node (ref "R15") (pin "2") (pinfunction "2_2") (pintype "passive"))
      (node (ref "U3") (pin "1") (pinfunction "OUT_1") (pintype "output"))
    )
    (net (code "41") (name "VBAT") (class "Default")
      (node (ref "C10") (pin "1") (pinfunction "1_1") (pintype "passive"))
      (node (ref "C11") (pin "1") (pinfunction "1_1") (pintype "passive"))
      (node (ref "C12") (pin "1") (pinfunction "1_1") (pintype "passive"))
      (node (ref "C13") (pin "1") (pinfunction "1_1") (pintype "passive"))
      (node (ref "C14") (pin "1") (pinfunction "1_1") (pintype "passive"))
      (node (ref "C17") (pin "1") (pinfunction "1_1") (pintype "passive"))
      (node (ref "C18") (pin "1") (pinfunction "1_1") (pintype "passive"))
      (node (ref "C19") (pin "1") (pinfunction "1_1") (pintype "passive"))
      (node (ref "C2") (pin "1") (pinfunction "1_1") (pintype "passive"))
      (node (ref "C20") (pin "1") (pinfunction "1_1") (pintype "passive"))
      (node (ref "C21") (pin "1") (pinfunction "1_1") (pintype "passive"))
      (node (ref "C22") (pin "1") (pinfunction "1_1") (pintype "passive"))
      (node (ref "C23") (pin "2") (pinfunction "2_2") (pintype "passive"))
      (node (ref "D1") (pin "1") (pinfunction "K_1") (pintype "passive"))
      (node (ref "Q1") (pin "5") (pinfunction "D_5") (pintype "passive"))
      (node (ref "Q2") (pin "5") (pinfunction "D_5") (pintype "passive"))
      (node (ref "Q3") (pin "5") (pinfunction "D_5") (pintype "passive"))
      (node (ref "R12") (pin "2") (pinfunction "2_2") (pintype "passive"))
      (node (ref "R13") (pin "2") (pinfunction "2_2") (pintype "passive"))
      (node (ref "U2") (pin "4") (pinfunction "GVDD_4") (pintype "power_in"))
      (node (ref "U3") (pin "4") (pinfunction "IN-_4") (pintype "power_in"))
      (node (ref "U4") (pin "1") (pinfunction "VIN_1") (pintype "passive"))
      (node (ref "U4") (pin "3") (pinfunction "EN_3") (pintype "passive"))
    )
    (net (code "42") (name "VIN") (class "Default")
      (node (ref "R12") (pin "1") (pinfunction "1_1") (pintype "passive"))
      (node (ref "U3") (pin "3") (pinfunction "IN+_3") (pintype "power_in"))
    )
    (net (code "43") (name "unconnected-(U1-PA0-Pad11)") (class "Default")
      (node (ref "U1") (pin "11") (pinfunction "PA0_11") (pintype "bidirectional"))
    )
    (net (code "44") (name "unconnected-(U1-PA1-Pad12)") (class "Default")
      (node (ref "U1") (pin "12") (pinfunction "PA1_12") (pintype "bidirectional"))
    )
    (net (code "45") (name "unconnected-(U1-PA5-Pad16)") (class "Default")
      (node (ref "U1") (pin "16") (pinfunction "PA5_16") (pintype "bidirectional"))
    )
    (net (code "46") (name "unconnected-(U1-PA11_[PA9]-Pad33)") (class "Default")
      (node (ref "U1") (pin "33") (pinfunction "PA11_[PA9]_33") (pintype "bidirectional"))
    )
    (net (code "47") (name "unconnected-(U1-PA12_[PA10]-Pad34)") (class "Default")
      (node (ref "U1") (pin "34") (pinfunction "PA12_[PA10]_34") (pintype "bidirectional"))
    )
    (net (code "48") (name "unconnected-(U1-PA15-Pad37)") (class "Default")
      (node (ref "U1") (pin "37") (pinfunction "PA15_37") (pintype "bidirectional"))
    )
    (net (code "49") (name "unconnected-(U1-PB2-Pad21)") (class "Default")
      (node (ref "U1") (pin "21") (pinfunction "PB2_21") (pintype "bidirectional"))
    )
    (net (code "50") (name "unconnected-(U1-PB5-Pad44)") (class "Default")
      (node (ref "U1") (pin "44") (pinfunction "PB5_44") (pintype "bidirectional"))
    )
    (net (code "51") (name "unconnected-(U1-PB8-Pad47)") (class "Default")
      (node (ref "U1") (pin "47") (pinfunction "PB8_47") (pintype "bidirectional"))
    )
    (net (code "52") (name "unconnected-(U1-PB9-Pad48)") (class "Default")
      (node (ref "U1") (pin "48") (pinfunction "PB9_48") (pintype "bidirectional"))
    )
    (net (code "53") (name "unconnected-(U1-PB10-Pad22)") (class "Default")
      (node (ref "U1") (pin "22") (pinfunction "PB10_22") (pintype "bidirectional"))
    )
    (net (code "54") (name "unconnected-(U1-PB11-Pad23)") (class "Default")
      (node (ref "U1") (pin "23") (pinfunction "PB11_23") (pintype "bidirectional"))
    )
    (net (code "55") (name "unconnected-(U1-PB12-Pad24)") (class "Default")
      (node (ref "U1") (pin "24") (pinfunction "PB12_24") (pintype "bidirectional"))
    )
    (net (code "56") (name "unconnected-(U1-PB13-Pad25)") (class "Default")
      (node (ref "U1") (pin "25") (pinfunction "PB13_25") (pintype "bidirectional"))
    )
    (net (code "57") (name "unconnected-(U1-PB14-Pad26)") (class "Default")
      (node (ref "U1") (pin "26") (pinfunction "PB14_26") (pintype "bidirectional"))
    )
    (net (code "58") (name "unconnected-(U1-PB15-Pad27)") (class "Default")
      (node (ref "U1") (pin "27") (pinfunction "PB15_27") (pintype "bidirectional"))
    )
    (net (code "59") (name "unconnected-(U1-PC6-Pad30)") (class "Default")
      (node (ref "U1") (pin "30") (pinfunction "PC6_30") (pintype "bidirectional"))
    )
    (net (code "60") (name "unconnected-(U1-PC7-Pad31)") (class "Default")
      (node (ref "U1") (pin "31") (pinfunction "PC7_31") (pintype "bidirectional"))
    )
    (net (code "61") (name "unconnected-(U1-PC13-Pad1)") (class "Default")
      (node (ref "U1") (pin "1") (pinfunction "PC13_1") (pintype "bidirectional"))
    )
    (net (code "62") (name "unconnected-(U1-PC14-OSC32_IN-Pad2)") (class "Default")
      (node (ref "U1") (pin "2") (pinfunction "PC14-OSC32_IN_2") (pintype "bidirectional"))
    )
    (net (code "63") (name "unconnected-(U1-PC15-OSC32_OUT-Pad3)") (class "Default")
      (node (ref "U1") (pin "3") (pinfunction "PC15-OSC32_OUT_3") (pintype "bidirectional"))
    )
    (net (code "64") (name "unconnected-(U1-PD0-Pad38)") (class "Default")
      (node (ref "U1") (pin "38") (pinfunction "PD0_38") (pintype "bidirectional"))
    )
    (net (code "65") (name "unconnected-(U1-PD1-Pad39)") (class "Default")
      (node (ref "U1") (pin "39") (pinfunction "PD1_39") (pintype "bidirectional"))
    )
    (net (code "66") (name "unconnected-(U1-PD2-Pad40)") (class "Default")
      (node (ref "U1") (pin "40") (pinfunction "PD2_40") (pintype "bidirectional"))
    )
    (net (code "67") (name "unconnected-(U1-PD3-Pad41)") (class "Default")
      (node (ref "U1") (pin "41") (pinfunction "PD3_41") (pintype "bidirectional"))
    )
    (net (code "68") (name "unconnected-(U1-PF0-OSC_IN-Pad8)") (class "Default")
      (node (ref "U1") (pin "8") (pinfunction "PF0-OSC_IN_8") (pintype "bidirectional"))
    )
    (net (code "69") (name "unconnected-(U1-PF1-OSC_OUT-Pad9)") (class "Default")
      (node (ref "U1") (pin "9") (pinfunction "PF1-OSC_OUT_9") (pintype "bidirectional"))
    )
    (net (code "70") (name "unconnected-(U2-MODE-Pad5)") (class "Default")
      (node (ref "U2") (pin "5") (pinfunction "MODE_5") (pintype "input+no_connect"))
    )
    (net (code "71") (name "unconnected-(U2-NC-Pad7)") (class "Default")
      (node (ref "U2") (pin "7") (pinfunction "NC_7") (pintype "passive+no_connect"))
    )
    (net (code "72") (name "unconnected-(U2-NC-Pad8)") (class "Default")
      (node (ref "U2") (pin "8") (pinfunction "NC_8") (pintype "passive+no_connect"))
    )
    (net (code "73") (name "unconnected-(U2-PowerPAD-Pad25)") (class "Default")
      (node (ref "U2") (pin "25") (pinfunction "PowerPAD_25") (pintype "power_in"))
    )
    (net (code "74") (name "unconnected-(U4-NC-Pad4)") (class "Default")
      (node (ref "U4") (pin "4") (pinfunction "NC_4") (pintype "passive+no_connect"))
    )
  )
)
